# SunS_Panels_Interfaces.net
KiCad netlist of a schematic drawn in Altium Designer
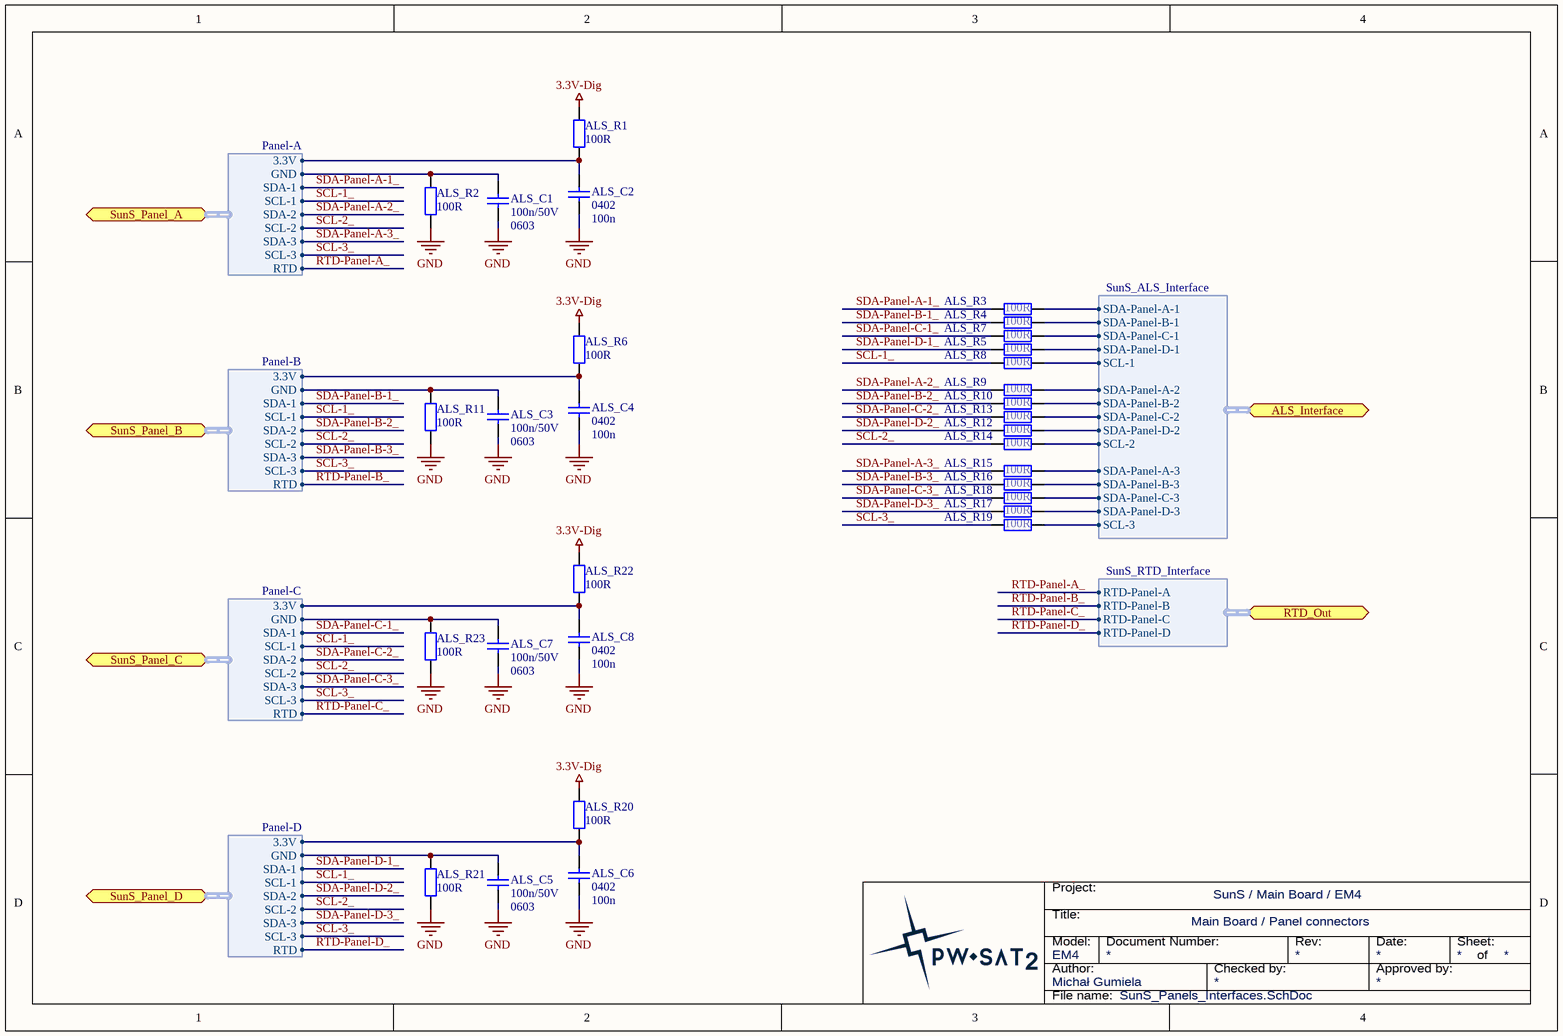
[diagram p0: SunS_Panels_Interfaces.SchDoc]

(export (version "E")
  (design (tool "Eeschema 10.0.6"))
  (components
    (comp (ref "ALS_C1")
      (value "100n/50V")
      (footprint "SMD_Capacitor_0603")
      (description "Cap")
      (fields (field (name "PACKAGE") "0603"))
      (libsource (lib "capacitors") (part "Cap"))
    )
    (comp (ref "ALS_C2")
      (value "0402")
      (footprint "SMD_Capacitor_0402")
      (description "Capacitor")
      (fields (field (name "ALTIUM_VALUE") "100n") (field (name "PUBLISHER") "Altium Limited"))
      (libsource (lib "Miscellaneous Devices") (part "Cap"))
    )
    (comp (ref "ALS_C3")
      (value "100n/50V")
      (footprint "SMD_Capacitor_0603")
      (description "Cap")
      (fields (field (name "PACKAGE") "0603"))
      (libsource (lib "capacitors") (part "Cap"))
    )
    (comp (ref "ALS_C4")
      (value "0402")
      (footprint "SMD_Capacitor_0402")
      (description "Capacitor")
      (fields (field (name "ALTIUM_VALUE") "100n") (field (name "PUBLISHER") "Altium Limited"))
      (libsource (lib "Miscellaneous Devices") (part "Cap"))
    )
    (comp (ref "ALS_C5")
      (value "100n/50V")
      (footprint "SMD_Capacitor_0603")
      (description "Cap")
      (fields (field (name "PACKAGE") "0603"))
      (libsource (lib "capacitors") (part "Cap"))
    )
    (comp (ref "ALS_C6")
      (value "0402")
      (footprint "SMD_Capacitor_0402")
      (description "Capacitor")
      (fields (field (name "ALTIUM_VALUE") "100n") (field (name "PUBLISHER") "Altium Limited"))
      (libsource (lib "Miscellaneous Devices") (part "Cap"))
    )
    (comp (ref "ALS_C7")
      (value "100n/50V")
      (footprint "SMD_Capacitor_0603")
      (description "Cap")
      (fields (field (name "PACKAGE") "0603"))
      (libsource (lib "capacitors") (part "Cap"))
    )
    (comp (ref "ALS_C8")
      (value "0402")
      (footprint "SMD_Capacitor_0402")
      (description "Capacitor")
      (fields (field (name "ALTIUM_VALUE") "100n") (field (name "PUBLISHER") "Altium Limited"))
      (libsource (lib "Miscellaneous Devices") (part "Cap"))
    )
    (comp (ref "ALS_R1")
      (value "100R")
      (footprint "SMD_Resistor_0402")
      (description "10R/1% Vishay CRCW 0402 Resistor. 63mW, 100ppm, 50V.")
      (fields
        (field (name "MANUFACTURER") "Vishay")
        (field (name "MANUFACTURERPARTNUMBER") "CRCW040210R0FKxxxx")
      )
      (libsource (lib "") (part "CRCW040210R0FKxxxx_1"))
    )
    (comp (ref "ALS_R2")
      (value "100R")
      (footprint "SMD_Resistor_0402")
      (description "10R/1% Vishay CRCW 0402 Resistor. 63mW, 100ppm, 50V.")
      (fields
        (field (name "MANUFACTURER") "Vishay")
        (field (name "MANUFACTURERPARTNUMBER") "CRCW040210R0FKxxxx")
      )
      (libsource (lib "") (part "CRCW040210R0FKxxxx_1"))
    )
    (comp (ref "ALS_R3")
      (value "100R")
      (footprint "SMD_Resistor_0402")
      (description "10R/1% Vishay CRCW 0402 Resistor. 63mW, 100ppm, 50V.")
      (fields
        (field (name "MANUFACTURER") "Vishay")
        (field (name "MANUFACTURERPARTNUMBER") "CRCW040210R0FKxxxx")
      )
      (libsource (lib "resistors") (part "CRCW040210R0FKxxxx"))
    )
    (comp (ref "ALS_R4")
      (value "100R")
      (footprint "SMD_Resistor_0402")
      (description "10R/1% Vishay CRCW 0402 Resistor. 63mW, 100ppm, 50V.")
      (fields
        (field (name "MANUFACTURER") "Vishay")
        (field (name "MANUFACTURERPARTNUMBER") "CRCW040210R0FKxxxx")
      )
      (libsource (lib "resistors") (part "CRCW040210R0FKxxxx"))
    )
    (comp (ref "ALS_R5")
      (value "100R")
      (footprint "SMD_Resistor_0402")
      (description "10R/1% Vishay CRCW 0402 Resistor. 63mW, 100ppm, 50V.")
      (fields
        (field (name "MANUFACTURER") "Vishay")
        (field (name "MANUFACTURERPARTNUMBER") "CRCW040210R0FKxxxx")
      )
      (libsource (lib "resistors") (part "CRCW040210R0FKxxxx"))
    )
    (comp (ref "ALS_R6")
      (value "100R")
      (footprint "SMD_Resistor_0402")
      (description "10R/1% Vishay CRCW 0402 Resistor. 63mW, 100ppm, 50V.")
      (fields
        (field (name "MANUFACTURER") "Vishay")
        (field (name "MANUFACTURERPARTNUMBER") "CRCW040210R0FKxxxx")
      )
      (libsource (lib "") (part "CRCW040210R0FKxxxx_1"))
    )
    (comp (ref "ALS_R7")
      (value "100R")
      (footprint "SMD_Resistor_0402")
      (description "10R/1% Vishay CRCW 0402 Resistor. 63mW, 100ppm, 50V.")
      (fields
        (field (name "MANUFACTURER") "Vishay")
        (field (name "MANUFACTURERPARTNUMBER") "CRCW040210R0FKxxxx")
      )
      (libsource (lib "resistors") (part "CRCW040210R0FKxxxx"))
    )
    (comp (ref "ALS_R8")
      (value "100R")
      (footprint "SMD_Resistor_0402")
      (description "10R/1% Vishay CRCW 0402 Resistor. 63mW, 100ppm, 50V.")
      (fields
        (field (name "MANUFACTURER") "Vishay")
        (field (name "MANUFACTURERPARTNUMBER") "CRCW040210R0FKxxxx")
      )
      (libsource (lib "resistors") (part "CRCW040210R0FKxxxx"))
    )
    (comp (ref "ALS_R9")
      (value "100R")
      (footprint "SMD_Resistor_0402")
      (description "10R/1% Vishay CRCW 0402 Resistor. 63mW, 100ppm, 50V.")
      (fields
        (field (name "MANUFACTURER") "Vishay")
        (field (name "MANUFACTURERPARTNUMBER") "CRCW040210R0FKxxxx")
      )
      (libsource (lib "resistors") (part "CRCW040210R0FKxxxx"))
    )
    (comp (ref "ALS_R10")
      (value "100R")
      (footprint "SMD_Resistor_0402")
      (description "10R/1% Vishay CRCW 0402 Resistor. 63mW, 100ppm, 50V.")
      (fields
        (field (name "MANUFACTURER") "Vishay")
        (field (name "MANUFACTURERPARTNUMBER") "CRCW040210R0FKxxxx")
      )
      (libsource (lib "resistors") (part "CRCW040210R0FKxxxx"))
    )
    (comp (ref "ALS_R11")
      (value "100R")
      (footprint "SMD_Resistor_0402")
      (description "10R/1% Vishay CRCW 0402 Resistor. 63mW, 100ppm, 50V.")
      (fields
        (field (name "MANUFACTURER") "Vishay")
        (field (name "MANUFACTURERPARTNUMBER") "CRCW040210R0FKxxxx")
      )
      (libsource (lib "") (part "CRCW040210R0FKxxxx_1"))
    )
    (comp (ref "ALS_R12")
      (value "100R")
      (footprint "SMD_Resistor_0402")
      (description "10R/1% Vishay CRCW 0402 Resistor. 63mW, 100ppm, 50V.")
      (fields
        (field (name "MANUFACTURER") "Vishay")
        (field (name "MANUFACTURERPARTNUMBER") "CRCW040210R0FKxxxx")
      )
      (libsource (lib "resistors") (part "CRCW040210R0FKxxxx"))
    )
    (comp (ref "ALS_R13")
      (value "100R")
      (footprint "SMD_Resistor_0402")
      (description "10R/1% Vishay CRCW 0402 Resistor. 63mW, 100ppm, 50V.")
      (fields
        (field (name "MANUFACTURER") "Vishay")
        (field (name "MANUFACTURERPARTNUMBER") "CRCW040210R0FKxxxx")
      )
      (libsource (lib "resistors") (part "CRCW040210R0FKxxxx"))
    )
    (comp (ref "ALS_R14")
      (value "100R")
      (footprint "SMD_Resistor_0402")
      (description "10R/1% Vishay CRCW 0402 Resistor. 63mW, 100ppm, 50V.")
      (fields
        (field (name "MANUFACTURER") "Vishay")
        (field (name "MANUFACTURERPARTNUMBER") "CRCW040210R0FKxxxx")
      )
      (libsource (lib "resistors") (part "CRCW040210R0FKxxxx"))
    )
    (comp (ref "ALS_R15")
      (value "100R")
      (footprint "SMD_Resistor_0402")
      (description "10R/1% Vishay CRCW 0402 Resistor. 63mW, 100ppm, 50V.")
      (fields
        (field (name "MANUFACTURER") "Vishay")
        (field (name "MANUFACTURERPARTNUMBER") "CRCW040210R0FKxxxx")
      )
      (libsource (lib "resistors") (part "CRCW040210R0FKxxxx"))
    )
    (comp (ref "ALS_R16")
      (value "100R")
      (footprint "SMD_Resistor_0402")
      (description "10R/1% Vishay CRCW 0402 Resistor. 63mW, 100ppm, 50V.")
      (fields
        (field (name "MANUFACTURER") "Vishay")
        (field (name "MANUFACTURERPARTNUMBER") "CRCW040210R0FKxxxx")
      )
      (libsource (lib "resistors") (part "CRCW040210R0FKxxxx"))
    )
    (comp (ref "ALS_R17")
      (value "100R")
      (footprint "SMD_Resistor_0402")
      (description "10R/1% Vishay CRCW 0402 Resistor. 63mW, 100ppm, 50V.")
      (fields
        (field (name "MANUFACTURER") "Vishay")
        (field (name "MANUFACTURERPARTNUMBER") "CRCW040210R0FKxxxx")
      )
      (libsource (lib "resistors") (part "CRCW040210R0FKxxxx"))
    )
    (comp (ref "ALS_R18")
      (value "100R")
      (footprint "SMD_Resistor_0402")
      (description "10R/1% Vishay CRCW 0402 Resistor. 63mW, 100ppm, 50V.")
      (fields
        (field (name "MANUFACTURER") "Vishay")
        (field (name "MANUFACTURERPARTNUMBER") "CRCW040210R0FKxxxx")
      )
      (libsource (lib "resistors") (part "CRCW040210R0FKxxxx"))
    )
    (comp (ref "ALS_R19")
      (value "100R")
      (footprint "SMD_Resistor_0402")
      (description "10R/1% Vishay CRCW 0402 Resistor. 63mW, 100ppm, 50V.")
      (fields
        (field (name "MANUFACTURER") "Vishay")
        (field (name "MANUFACTURERPARTNUMBER") "CRCW040210R0FKxxxx")
      )
      (libsource (lib "resistors") (part "CRCW040210R0FKxxxx"))
    )
    (comp (ref "ALS_R20")
      (value "100R")
      (footprint "SMD_Resistor_0402")
      (description "10R/1% Vishay CRCW 0402 Resistor. 63mW, 100ppm, 50V.")
      (fields
        (field (name "MANUFACTURER") "Vishay")
        (field (name "MANUFACTURERPARTNUMBER") "CRCW040210R0FKxxxx")
      )
      (libsource (lib "") (part "CRCW040210R0FKxxxx_1"))
    )
    (comp (ref "ALS_R21")
      (value "100R")
      (footprint "SMD_Resistor_0402")
      (description "10R/1% Vishay CRCW 0402 Resistor. 63mW, 100ppm, 50V.")
      (fields
        (field (name "MANUFACTURER") "Vishay")
        (field (name "MANUFACTURERPARTNUMBER") "CRCW040210R0FKxxxx")
      )
      (libsource (lib "") (part "CRCW040210R0FKxxxx_1"))
    )
    (comp (ref "ALS_R22")
      (value "100R")
      (footprint "SMD_Resistor_0402")
      (description "10R/1% Vishay CRCW 0402 Resistor. 63mW, 100ppm, 50V.")
      (fields
        (field (name "MANUFACTURER") "Vishay")
        (field (name "MANUFACTURERPARTNUMBER") "CRCW040210R0FKxxxx")
      )
      (libsource (lib "") (part "CRCW040210R0FKxxxx_1"))
    )
    (comp (ref "ALS_R23")
      (value "100R")
      (footprint "SMD_Resistor_0402")
      (description "10R/1% Vishay CRCW 0402 Resistor. 63mW, 100ppm, 50V.")
      (fields
        (field (name "MANUFACTURER") "Vishay")
        (field (name "MANUFACTURERPARTNUMBER") "CRCW040210R0FKxxxx")
      )
      (libsource (lib "") (part "CRCW040210R0FKxxxx_1"))
    )
  )
  (nets
    (net (code "11") (name "/SCL-1_") (class "Default")
      (node (ref "ALS_R8") (pin "2") (pinfunction "2_2") (pintype "passive"))
    )
    (net (code "12") (name "/SCL-2_") (class "Default")
      (node (ref "ALS_R14") (pin "2") (pinfunction "2_2") (pintype "passive"))
    )
    (net (code "13") (name "/SCL-3_") (class "Default")
      (node (ref "ALS_R19") (pin "2") (pinfunction "2_2") (pintype "passive"))
    )
    (net (code "14") (name "/SDA-Panel-A-1") (class "Default")
      (node (ref "ALS_R3") (pin "1") (pinfunction "1_1") (pintype "passive"))
    )
    (net (code "15") (name "/SDA-Panel-A-1_") (class "Default")
      (node (ref "ALS_R3") (pin "2") (pinfunction "2_2") (pintype "passive"))
    )
    (net (code "16") (name "/SDA-Panel-A-2") (class "Default")
      (node (ref "ALS_R9") (pin "1") (pinfunction "1_1") (pintype "passive"))
    )
    (net (code "17") (name "/SDA-Panel-A-2_") (class "Default")
      (node (ref "ALS_R9") (pin "2") (pinfunction "2_2") (pintype "passive"))
    )
    (net (code "18") (name "/SDA-Panel-A-3") (class "Default")
      (node (ref "ALS_R15") (pin "1") (pinfunction "1_1") (pintype "passive"))
    )
    (net (code "19") (name "/SDA-Panel-A-3_") (class "Default")
      (node (ref "ALS_R15") (pin "2") (pinfunction "2_2") (pintype "passive"))
    )
    (net (code "20") (name "/SDA-Panel-B-1") (class "Default")
      (node (ref "ALS_R4") (pin "1") (pinfunction "1_1") (pintype "passive"))
    )
    (net (code "21") (name "/SDA-Panel-B-1_") (class "Default")
      (node (ref "ALS_R4") (pin "2") (pinfunction "2_2") (pintype "passive"))
    )
    (net (code "22") (name "/SDA-Panel-B-2") (class "Default")
      (node (ref "ALS_R10") (pin "1") (pinfunction "1_1") (pintype "passive"))
    )
    (net (code "23") (name "/SDA-Panel-B-2_") (class "Default")
      (node (ref "ALS_R10") (pin "2") (pinfunction "2_2") (pintype "passive"))
    )
    (net (code "24") (name "/SDA-Panel-B-3") (class "Default")
      (node (ref "ALS_R16") (pin "1") (pinfunction "1_1") (pintype "passive"))
    )
    (net (code "25") (name "/SDA-Panel-B-3_") (class "Default")
      (node (ref "ALS_R16") (pin "2") (pinfunction "2_2") (pintype "passive"))
    )
    (net (code "26") (name "/SDA-Panel-C-1") (class "Default")
      (node (ref "ALS_R7") (pin "1") (pinfunction "1_1") (pintype "passive"))
    )
    (net (code "27") (name "/SDA-Panel-C-1_") (class "Default")
      (node (ref "ALS_R7") (pin "2") (pinfunction "2_2") (pintype "passive"))
    )
    (net (code "28") (name "/SDA-Panel-C-2") (class "Default")
      (node (ref "ALS_R13") (pin "1") (pinfunction "1_1") (pintype "passive"))
    )
    (net (code "29") (name "/SDA-Panel-C-2_") (class "Default")
      (node (ref "ALS_R13") (pin "2") (pinfunction "2_2") (pintype "passive"))
    )
    (net (code "30") (name "/SDA-Panel-C-3") (class "Default")
      (node (ref "ALS_R18") (pin "1") (pinfunction "1_1") (pintype "passive"))
    )
    (net (code "31") (name "/SDA-Panel-C-3_") (class "Default")
      (node (ref "ALS_R18") (pin "2") (pinfunction "2_2") (pintype "passive"))
    )
    (net (code "32") (name "/SDA-Panel-D-1") (class "Default")
      (node (ref "ALS_R5") (pin "1") (pinfunction "1_1") (pintype "passive"))
    )
    (net (code "33") (name "/SDA-Panel-D-1_") (class "Default")
      (node (ref "ALS_R5") (pin "2") (pinfunction "2_2") (pintype "passive"))
    )
    (net (code "34") (name "/SDA-Panel-D-2") (class "Default")
      (node (ref "ALS_R12") (pin "1") (pinfunction "1_1") (pintype "passive"))
    )
    (net (code "35") (name "/SDA-Panel-D-2_") (class "Default")
      (node (ref "ALS_R12") (pin "2") (pinfunction "2_2") (pintype "passive"))
    )
    (net (code "36") (name "/SDA-Panel-D-3") (class "Default")
      (node (ref "ALS_R17") (pin "1") (pinfunction "1_1") (pintype "passive"))
    )
    (net (code "37") (name "/SDA-Panel-D-3_") (class "Default")
      (node (ref "ALS_R17") (pin "2") (pinfunction "2_2") (pintype "passive"))
    )
    (net (code "44") (name "3.3V-Dig") (class "Default")
      (node (ref "ALS_R1") (pin "2") (pinfunction "2_2") (pintype "passive"))
      (node (ref "ALS_R20") (pin "2") (pinfunction "2_2") (pintype "passive"))
      (node (ref "ALS_R22") (pin "2") (pinfunction "2_2") (pintype "passive"))
      (node (ref "ALS_R6") (pin "2") (pinfunction "2_2") (pintype "passive"))
    )
    (net (code "45") (name "GND") (class "Default")
      (node (ref "ALS_C1") (pin "2") (pinfunction "2_2") (pintype "passive"))
      (node (ref "ALS_C2") (pin "1") (pinfunction "1_1") (pintype "passive"))
      (node (ref "ALS_C3") (pin "2") (pinfunction "2_2") (pintype "passive"))
      (node (ref "ALS_C4") (pin "1") (pinfunction "1_1") (pintype "passive"))
      (node (ref "ALS_C5") (pin "2") (pinfunction "2_2") (pintype "passive"))
      (node (ref "ALS_C6") (pin "1") (pinfunction "1_1") (pintype "passive"))
      (node (ref "ALS_C7") (pin "2") (pinfunction "2_2") (pintype "passive"))
      (node (ref "ALS_C8") (pin "1") (pinfunction "1_1") (pintype "passive"))
      (node (ref "ALS_R11") (pin "1") (pinfunction "1_1") (pintype "passive"))
      (node (ref "ALS_R2") (pin "1") (pinfunction "1_1") (pintype "passive"))
      (node (ref "ALS_R21") (pin "1") (pinfunction "1_1") (pintype "passive"))
      (node (ref "ALS_R23") (pin "1") (pinfunction "1_1") (pintype "passive"))
    )
    (net (code "46") (name "Net-(ALS_C1-Pad1)") (class "Default")
      (node (ref "ALS_C1") (pin "1") (pinfunction "1_1") (pintype "passive"))
      (node (ref "ALS_R2") (pin "2") (pinfunction "2_2") (pintype "passive"))
    )
    (net (code "47") (name "Net-(ALS_C2-Pad2)") (class "Default")
      (node (ref "ALS_C2") (pin "2") (pinfunction "2_2") (pintype "passive"))
      (node (ref "ALS_R1") (pin "1") (pinfunction "1_1") (pintype "passive"))
    )
    (net (code "48") (name "Net-(ALS_C3-Pad1)") (class "Default")
      (node (ref "ALS_C3") (pin "1") (pinfunction "1_1") (pintype "passive"))
      (node (ref "ALS_R11") (pin "2") (pinfunction "2_2") (pintype "passive"))
    )
    (net (code "49") (name "Net-(ALS_C4-Pad2)") (class "Default")
      (node (ref "ALS_C4") (pin "2") (pinfunction "2_2") (pintype "passive"))
      (node (ref "ALS_R6") (pin "1") (pinfunction "1_1") (pintype "passive"))
    )
    (net (code "50") (name "Net-(ALS_C5-Pad1)") (class "Default")
      (node (ref "ALS_C5") (pin "1") (pinfunction "1_1") (pintype "passive"))
      (node (ref "ALS_R21") (pin "2") (pinfunction "2_2") (pintype "passive"))
    )
    (net (code "51") (name "Net-(ALS_C6-Pad2)") (class "Default")
      (node (ref "ALS_C6") (pin "2") (pinfunction "2_2") (pintype "passive"))
      (node (ref "ALS_R20") (pin "1") (pinfunction "1_1") (pintype "passive"))
    )
    (net (code "52") (name "Net-(ALS_C7-Pad1)") (class "Default")
      (node (ref "ALS_C7") (pin "1") (pinfunction "1_1") (pintype "passive"))
      (node (ref "ALS_R23") (pin "2") (pinfunction "2_2") (pintype "passive"))
    )
    (net (code "53") (name "Net-(ALS_C8-Pad2)") (class "Default")
      (node (ref "ALS_C8") (pin "2") (pinfunction "2_2") (pintype "passive"))
      (node (ref "ALS_R22") (pin "1") (pinfunction "1_1") (pintype "passive"))
    )
    (net (code "54") (name "unconnected-(ALS_R8-Pad1)") (class "Default")
      (node (ref "ALS_R8") (pin "1") (pinfunction "1_1") (pintype "passive"))
    )
    (net (code "55") (name "unconnected-(ALS_R14-Pad1)") (class "Default")
      (node (ref "ALS_R14") (pin "1") (pinfunction "1_1") (pintype "passive"))
    )
    (net (code "56") (name "unconnected-(ALS_R19-Pad1)") (class "Default")
      (node (ref "ALS_R19") (pin "1") (pinfunction "1_1") (pintype "passive"))
    )
  )
)
